# main.net
KiCad netlist of a schematic drawn in EAGLE
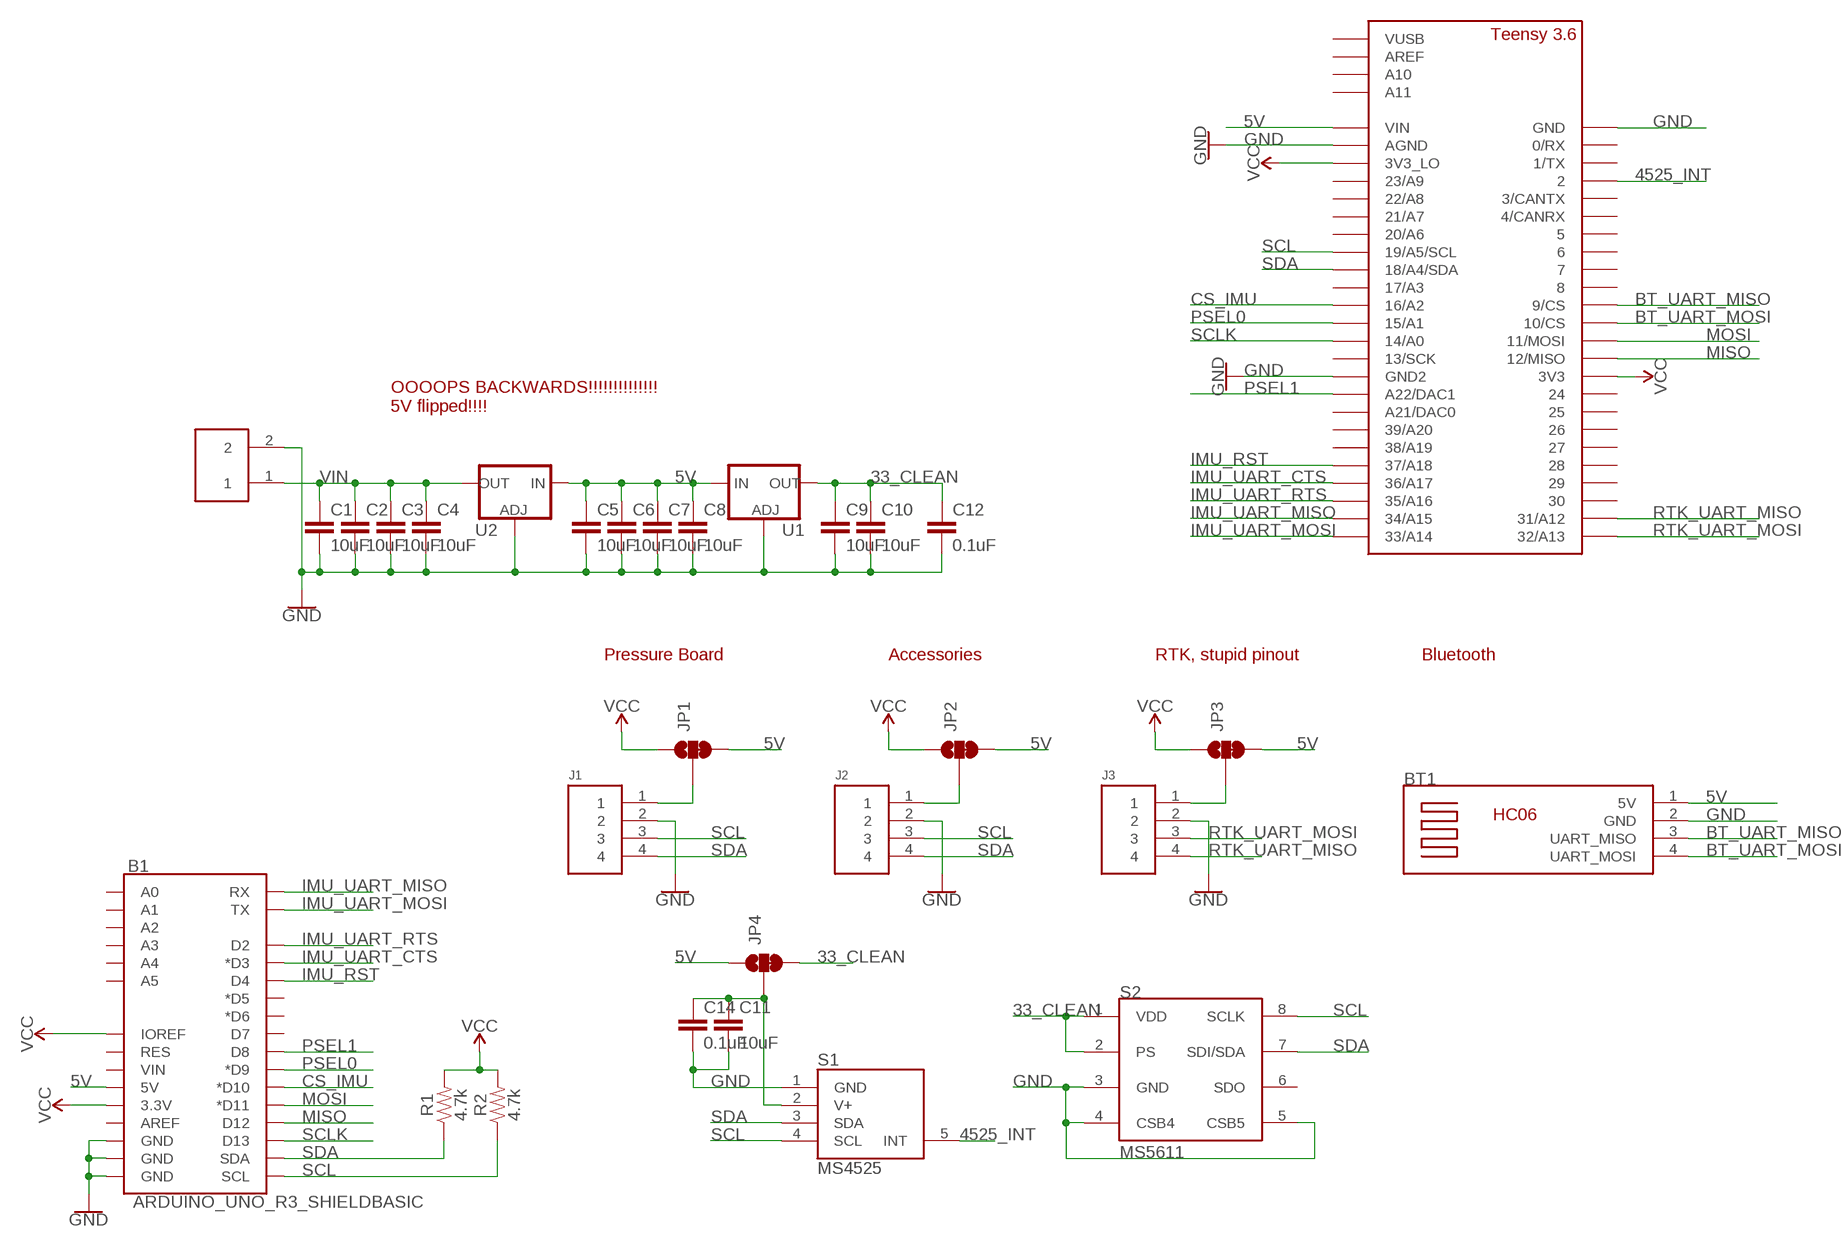
[diagram p0: schematic, sheet 1]

(export (version "E")
  (design (tool "Eeschema 10.0.6"))
  (components
    (comp (ref "B1")
      (value "ARDUINO_UNO_R3_SHIELDBASIC")
      (footprint "eagle-import:UNO_R3_SHIELD")
      (libsource (lib "eagle-import") (part "ARDUINO_UNO_R3_SHIELDBASIC"))
    )
    (comp (ref "BT1")
      (value "HC06")
      (footprint "eagle-import:HC06")
      (libsource (lib "eagle-import") (part "HC06"))
    )
    (comp (ref "C1")
      (value "10uF")
      (footprint "eagle-import:1206")
      (libsource (lib "eagle-import") (part "10UF-1206-6.3V-20%"))
    )
    (comp (ref "C2")
      (value "10uF")
      (footprint "eagle-import:1206")
      (libsource (lib "eagle-import") (part "10UF-1206-6.3V-20%"))
    )
    (comp (ref "C3")
      (value "10uF")
      (footprint "eagle-import:1206")
      (libsource (lib "eagle-import") (part "10UF-1206-6.3V-20%"))
    )
    (comp (ref "C4")
      (value "10uF")
      (footprint "eagle-import:1206")
      (libsource (lib "eagle-import") (part "10UF-1206-6.3V-20%"))
    )
    (comp (ref "C5")
      (value "10uF")
      (footprint "eagle-import:1206")
      (libsource (lib "eagle-import") (part "10UF-1206-6.3V-20%"))
    )
    (comp (ref "C6")
      (value "10uF")
      (footprint "eagle-import:1206")
      (libsource (lib "eagle-import") (part "10UF-1206-6.3V-20%"))
    )
    (comp (ref "C7")
      (value "10uF")
      (footprint "eagle-import:1206")
      (libsource (lib "eagle-import") (part "10UF-1206-6.3V-20%"))
    )
    (comp (ref "C8")
      (value "10uF")
      (footprint "eagle-import:1206")
      (libsource (lib "eagle-import") (part "10UF-1206-6.3V-20%"))
    )
    (comp (ref "C9")
      (value "10uF")
      (footprint "eagle-import:1206")
      (libsource (lib "eagle-import") (part "10UF-1206-6.3V-20%"))
    )
    (comp (ref "C10")
      (value "10uF")
      (footprint "eagle-import:1206")
      (libsource (lib "eagle-import") (part "10UF-1206-6.3V-20%"))
    )
    (comp (ref "C11")
      (value "10uF")
      (footprint "eagle-import:1206")
      (libsource (lib "eagle-import") (part "10UF-1206-6.3V-20%"))
    )
    (comp (ref "C12")
      (value "0.1uF")
      (footprint "eagle-import:0603")
      (libsource (lib "eagle-import") (part "0.1UF-0603-25V-5%"))
    )
    (comp (ref "C14")
      (value "0.1uF")
      (footprint "eagle-import:0603")
      (libsource (lib "eagle-import") (part "0.1UF-0603-25V-5%"))
    )
    (comp (ref "J1")
      (value "HEADER4VALULOK")
      (footprint "eagle-import:4PINVALULOK")
      (libsource (lib "eagle-import") (part "HEADER4VALULOK"))
    )
    (comp (ref "J2")
      (value "HEADER4VALULOK")
      (footprint "eagle-import:4PINVALULOK")
      (libsource (lib "eagle-import") (part "HEADER4VALULOK"))
    )
    (comp (ref "J3")
      (value "HEADER4VALULOK")
      (footprint "eagle-import:4PINVALULOK")
      (libsource (lib "eagle-import") (part "HEADER4VALULOK"))
    )
    (comp (ref "JP1")
      (value "JUMPER-SMT_3_1-NC_TRACE_SILK")
      (footprint "eagle-import:SMT-JUMPER_3_1-NC_TRACE_SILK")
      (libsource (lib "eagle-import") (part "JUMPER-SMT_3_1-NC_TRACE_SILK"))
    )
    (comp (ref "JP2")
      (value "JUMPER-SMT_3_1-NC_TRACE_SILK")
      (footprint "eagle-import:SMT-JUMPER_3_1-NC_TRACE_SILK")
      (libsource (lib "eagle-import") (part "JUMPER-SMT_3_1-NC_TRACE_SILK"))
    )
    (comp (ref "JP3")
      (value "JUMPER-SMT_3_1-NC_TRACE_SILK")
      (footprint "eagle-import:SMT-JUMPER_3_1-NC_TRACE_SILK")
      (libsource (lib "eagle-import") (part "JUMPER-SMT_3_1-NC_TRACE_SILK"))
    )
    (comp (ref "JP4")
      (value "JUMPER-SMT_3_1-NC_TRACE_SILK")
      (footprint "eagle-import:SMT-JUMPER_3_1-NC_TRACE_SILK")
      (libsource (lib "eagle-import") (part "JUMPER-SMT_3_1-NC_TRACE_SILK"))
    )
    (comp (ref "R1")
      (value "4.7k")
      (footprint "eagle-import:0603")
      (libsource (lib "eagle-import") (part "4.7KOHM-0603-1/10W-1%"))
    )
    (comp (ref "R2")
      (value "4.7k")
      (footprint "eagle-import:0603")
      (libsource (lib "eagle-import") (part "4.7KOHM-0603-1/10W-1%"))
    )
    (comp (ref "S1")
      (value "MS4525")
      (footprint "eagle-import:DIP1270W53P254L990H762Q8B")
      (libsource (lib "eagle-import") (part "MS4525MS4525DO"))
    )
    (comp (ref "S2")
      (value "MS5611")
      (footprint "eagle-import:MS5611")
      (libsource (lib "eagle-import") (part "MS5611"))
    )
    (comp (ref "U$1")
      (value "TEENSY_3.5/3.6_BASIC")
      (footprint "eagle-import:TEENSY_3.5_3.6_BASIC")
      (libsource (lib "eagle-import") (part "TEENSY_3.5/3.6_BASIC"))
    )
    (comp (ref "U$3")
      (value "HEADER2")
      (footprint "eagle-import:2PINVALULOK")
      (libsource (lib "eagle-import") (part "HEADER2"))
    )
    (comp (ref "U1")
      (value "V_REG_317SMD")
      (footprint "eagle-import:SOT223")
      (libsource (lib "eagle-import") (part "V_REG_317SMD"))
    )
    (comp (ref "U2")
      (value "V_REG_317DPACK")
      (footprint "eagle-import:V-REG_DPACK")
      (libsource (lib "eagle-import") (part "V_REG_317DPACK"))
    )
  )
  (nets
    (net (code "1") (name "/5V") (class "Default")
      (node (ref "B1") (pin "5V") (pinfunction "5V_5V") (pintype "bidirectional"))
      (node (ref "BT1") (pin "1") (pinfunction "5V_1") (pintype "bidirectional"))
      (node (ref "C5") (pin "1") (pinfunction "1_1") (pintype "passive"))
      (node (ref "C6") (pin "1") (pinfunction "1_1") (pintype "passive"))
      (node (ref "C7") (pin "1") (pinfunction "1_1") (pintype "passive"))
      (node (ref "C8") (pin "1") (pinfunction "1_1") (pintype "passive"))
      (node (ref "JP1") (pin "3") (pinfunction "3_3") (pintype "passive"))
      (node (ref "JP2") (pin "3") (pinfunction "3_3") (pintype "passive"))
      (node (ref "JP3") (pin "3") (pinfunction "3_3") (pintype "passive"))
      (node (ref "JP4") (pin "1") (pinfunction "1_1") (pintype "passive"))
      (node (ref "U$1") (pin "VIN") (pinfunction "VIN_VIN") (pintype "bidirectional"))
      (node (ref "U1") (pin "3") (pinfunction "IN_3") (pintype "input"))
      (node (ref "U2") (pin "3") (pinfunction "IN_3") (pintype "input"))
    )
    (net (code "2") (name "/33_CLEAN") (class "Default")
      (node (ref "C10") (pin "1") (pinfunction "1_1") (pintype "passive"))
      (node (ref "C12") (pin "1") (pinfunction "1_1") (pintype "passive"))
      (node (ref "C9") (pin "1") (pinfunction "1_1") (pintype "passive"))
      (node (ref "JP4") (pin "3") (pinfunction "3_3") (pintype "passive"))
      (node (ref "S2") (pin "1") (pinfunction "VDD_1") (pintype "bidirectional"))
      (node (ref "S2") (pin "2") (pinfunction "PS_2") (pintype "bidirectional"))
      (node (ref "U1") (pin "2") (pinfunction "OUT_2") (pintype "output"))
    )
    (net (code "3") (name "/4525_INT") (class "Default")
      (node (ref "S1") (pin "5") (pinfunction "INT_5") (pintype "bidirectional"))
      (node (ref "U$1") (pin "2") (pinfunction "2_2") (pintype "bidirectional"))
    )
    (net (code "4") (name "/BT_UART_MISO") (class "Default")
      (node (ref "BT1") (pin "3") (pinfunction "UART_MISO_3") (pintype "bidirectional"))
      (node (ref "U$1") (pin "9/CS") (pinfunction "9/CS_9/CS") (pintype "bidirectional"))
    )
    (net (code "5") (name "/BT_UART_MOSI") (class "Default")
      (node (ref "BT1") (pin "4") (pinfunction "UART_MOSI_4") (pintype "bidirectional"))
      (node (ref "U$1") (pin "10/CS") (pinfunction "10/CS_10/CS") (pintype "bidirectional"))
    )
    (net (code "6") (name "/CS_IMU") (class "Default")
      (node (ref "B1") (pin "D10") (pinfunction "*D10_D10") (pintype "bidirectional"))
      (node (ref "U$1") (pin "16/A2") (pinfunction "16/A2_16/A2") (pintype "bidirectional"))
    )
    (net (code "7") (name "/IMU_RST") (class "Default")
      (node (ref "B1") (pin "D4") (pinfunction "D4_D4") (pintype "bidirectional"))
      (node (ref "U$1") (pin "37/A18") (pinfunction "37/A18_37/A18") (pintype "bidirectional"))
    )
    (net (code "8") (name "/IMU_UART_CTS") (class "Default")
      (node (ref "B1") (pin "D3") (pinfunction "*D3_D3") (pintype "bidirectional"))
      (node (ref "U$1") (pin "36/A17") (pinfunction "36/A17_36/A17") (pintype "bidirectional"))
    )
    (net (code "9") (name "/IMU_UART_MISO") (class "Default")
      (node (ref "B1") (pin "RX") (pinfunction "RX_RX") (pintype "bidirectional"))
      (node (ref "U$1") (pin "34/A15") (pinfunction "34/A15_34/A15") (pintype "bidirectional"))
    )
    (net (code "10") (name "/IMU_UART_MOSI") (class "Default")
      (node (ref "B1") (pin "TX") (pinfunction "TX_TX") (pintype "bidirectional"))
      (node (ref "U$1") (pin "33/A14") (pinfunction "33/A14_33/A14") (pintype "bidirectional"))
    )
    (net (code "11") (name "/IMU_UART_RTS") (class "Default")
      (node (ref "B1") (pin "D2") (pinfunction "D2_D2") (pintype "bidirectional"))
      (node (ref "U$1") (pin "35/A16") (pinfunction "35/A16_35/A16") (pintype "bidirectional"))
    )
    (net (code "12") (name "/MISO") (class "Default")
      (node (ref "B1") (pin "D12") (pinfunction "D12_D12") (pintype "bidirectional"))
      (node (ref "U$1") (pin "12/MISO") (pinfunction "12/MISO_12/MISO") (pintype "bidirectional"))
    )
    (net (code "13") (name "/MOSI") (class "Default")
      (node (ref "B1") (pin "D11") (pinfunction "*D11_D11") (pintype "bidirectional"))
      (node (ref "U$1") (pin "11/MOSI") (pinfunction "11/MOSI_11/MOSI") (pintype "bidirectional"))
    )
    (net (code "14") (name "/PSEL0") (class "Default")
      (node (ref "B1") (pin "D9") (pinfunction "*D9_D9") (pintype "bidirectional"))
      (node (ref "U$1") (pin "15/A1") (pinfunction "15/A1_15/A1") (pintype "bidirectional"))
    )
    (net (code "15") (name "/PSEL1") (class "Default")
      (node (ref "B1") (pin "D8") (pinfunction "D8_D8") (pintype "bidirectional"))
      (node (ref "U$1") (pin "A22/DAC1") (pinfunction "A22/DAC1_A22/DAC1") (pintype "bidirectional"))
    )
    (net (code "16") (name "/RTK_UART_MISO") (class "Default")
      (node (ref "J3") (pin "4") (pinfunction "4_4") (pintype "bidirectional"))
      (node (ref "U$1") (pin "31/A12") (pinfunction "31/A12_31/A12") (pintype "bidirectional"))
    )
    (net (code "17") (name "/RTK_UART_MOSI") (class "Default")
      (node (ref "J3") (pin "3") (pinfunction "3_3") (pintype "bidirectional"))
      (node (ref "U$1") (pin "32/A13") (pinfunction "32/A13_32/A13") (pintype "bidirectional"))
    )
    (net (code "18") (name "/SCL") (class "Default")
      (node (ref "B1") (pin "SCL") (pinfunction "SCL_SCL") (pintype "bidirectional"))
      (node (ref "J1") (pin "3") (pinfunction "3_3") (pintype "bidirectional"))
      (node (ref "J2") (pin "3") (pinfunction "3_3") (pintype "bidirectional"))
      (node (ref "R2") (pin "1") (pinfunction "1_1") (pintype "passive"))
      (node (ref "S1") (pin "4") (pinfunction "SCL_4") (pintype "bidirectional"))
      (node (ref "S2") (pin "8") (pinfunction "SCLK_8") (pintype "bidirectional"))
      (node (ref "U$1") (pin "19/A5/SCL") (pinfunction "19/A5/SCL_19/A5/SCL") (pintype "bidirectional"))
    )
    (net (code "19") (name "/SCLK") (class "Default")
      (node (ref "B1") (pin "D13") (pinfunction "D13_D13") (pintype "bidirectional"))
      (node (ref "U$1") (pin "14/A0") (pinfunction "14/A0_14/A0") (pintype "bidirectional"))
    )
    (net (code "20") (name "/SDA") (class "Default")
      (node (ref "B1") (pin "SDA") (pinfunction "SDA_SDA") (pintype "bidirectional"))
      (node (ref "J1") (pin "4") (pinfunction "4_4") (pintype "bidirectional"))
      (node (ref "J2") (pin "4") (pinfunction "4_4") (pintype "bidirectional"))
      (node (ref "R1") (pin "1") (pinfunction "1_1") (pintype "passive"))
      (node (ref "S1") (pin "3") (pinfunction "SDA_3") (pintype "bidirectional"))
      (node (ref "S2") (pin "7") (pinfunction "SDI/SDA_7") (pintype "bidirectional"))
      (node (ref "U$1") (pin "18/A4/SDA") (pinfunction "18/A4/SDA_18/A4/SDA") (pintype "bidirectional"))
    )
    (net (code "21") (name "/VIN") (class "Default")
      (node (ref "C1") (pin "1") (pinfunction "1_1") (pintype "passive"))
      (node (ref "C2") (pin "1") (pinfunction "1_1") (pintype "passive"))
      (node (ref "C3") (pin "1") (pinfunction "1_1") (pintype "passive"))
      (node (ref "C4") (pin "1") (pinfunction "1_1") (pintype "passive"))
      (node (ref "U$3") (pin "1") (pinfunction "1_1") (pintype "bidirectional"))
      (node (ref "U2") (pin "4") (pinfunction "OUT_4") (pintype "output"))
    )
    (net (code "22") (name "GND") (class "Default")
      (node (ref "B1") (pin "GND@0") (pinfunction "GND_GND@0") (pintype "bidirectional"))
      (node (ref "B1") (pin "GND@1") (pinfunction "GND_GND@1") (pintype "bidirectional"))
      (node (ref "B1") (pin "GND@2") (pinfunction "GND_GND@2") (pintype "bidirectional"))
      (node (ref "BT1") (pin "2") (pinfunction "GND_2") (pintype "bidirectional"))
      (node (ref "C1") (pin "2") (pinfunction "2_2") (pintype "passive"))
      (node (ref "C10") (pin "2") (pinfunction "2_2") (pintype "passive"))
      (node (ref "C11") (pin "2") (pinfunction "2_2") (pintype "passive"))
      (node (ref "C12") (pin "2") (pinfunction "2_2") (pintype "passive"))
      (node (ref "C14") (pin "2") (pinfunction "2_2") (pintype "passive"))
      (node (ref "C2") (pin "2") (pinfunction "2_2") (pintype "passive"))
      (node (ref "C3") (pin "2") (pinfunction "2_2") (pintype "passive"))
      (node (ref "C4") (pin "2") (pinfunction "2_2") (pintype "passive"))
      (node (ref "C5") (pin "2") (pinfunction "2_2") (pintype "passive"))
      (node (ref "C6") (pin "2") (pinfunction "2_2") (pintype "passive"))
      (node (ref "C7") (pin "2") (pinfunction "2_2") (pintype "passive"))
      (node (ref "C8") (pin "2") (pinfunction "2_2") (pintype "passive"))
      (node (ref "C9") (pin "2") (pinfunction "2_2") (pintype "passive"))
      (node (ref "J1") (pin "2") (pinfunction "2_2") (pintype "bidirectional"))
      (node (ref "J2") (pin "2") (pinfunction "2_2") (pintype "bidirectional"))
      (node (ref "J3") (pin "2") (pinfunction "2_2") (pintype "bidirectional"))
      (node (ref "S1") (pin "1") (pinfunction "GND_1") (pintype "bidirectional"))
      (node (ref "S2") (pin "3") (pinfunction "GND_3") (pintype "bidirectional"))
      (node (ref "S2") (pin "4") (pinfunction "CSB4_4") (pintype "bidirectional"))
      (node (ref "S2") (pin "5") (pinfunction "CSB5_5") (pintype "bidirectional"))
      (node (ref "U$1") (pin "AGND") (pinfunction "AGND_AGND") (pintype "bidirectional"))
      (node (ref "U$1") (pin "GND") (pinfunction "GND_GND") (pintype "bidirectional"))
      (node (ref "U$1") (pin "GND2") (pinfunction "GND2_GND2") (pintype "bidirectional"))
      (node (ref "U$3") (pin "2") (pinfunction "2_2") (pintype "bidirectional"))
      (node (ref "U1") (pin "1") (pinfunction "ADJ_1") (pintype "input"))
      (node (ref "U2") (pin "1") (pinfunction "ADJ_1") (pintype "input"))
    )
    (net (code "23") (name "Net-(J1-Pad1)") (class "Default")
      (node (ref "J1") (pin "1") (pinfunction "1_1") (pintype "bidirectional"))
      (node (ref "JP1") (pin "2") (pinfunction "2_2") (pintype "passive"))
    )
    (net (code "24") (name "Net-(J2-Pad1)") (class "Default")
      (node (ref "J2") (pin "1") (pinfunction "1_1") (pintype "bidirectional"))
      (node (ref "JP2") (pin "2") (pinfunction "2_2") (pintype "passive"))
    )
    (net (code "25") (name "Net-(J3-Pad1)") (class "Default")
      (node (ref "J3") (pin "1") (pinfunction "1_1") (pintype "bidirectional"))
      (node (ref "JP3") (pin "2") (pinfunction "2_2") (pintype "passive"))
    )
    (net (code "26") (name "Net-(S1-V+)") (class "Default")
      (node (ref "C11") (pin "1") (pinfunction "1_1") (pintype "passive"))
      (node (ref "C14") (pin "1") (pinfunction "1_1") (pintype "passive"))
      (node (ref "JP4") (pin "2") (pinfunction "2_2") (pintype "passive"))
      (node (ref "S1") (pin "2") (pinfunction "V+_2") (pintype "bidirectional"))
    )
    (net (code "27") (name "VCC") (class "Default")
      (node (ref "B1") (pin "3.3V") (pinfunction "3.3V_3.3V") (pintype "bidirectional"))
      (node (ref "B1") (pin "IOREF") (pinfunction "IOREF_IOREF") (pintype "bidirectional"))
      (node (ref "JP1") (pin "1") (pinfunction "1_1") (pintype "passive"))
      (node (ref "JP2") (pin "1") (pinfunction "1_1") (pintype "passive"))
      (node (ref "JP3") (pin "1") (pinfunction "1_1") (pintype "passive"))
      (node (ref "R1") (pin "2") (pinfunction "2_2") (pintype "passive"))
      (node (ref "R2") (pin "2") (pinfunction "2_2") (pintype "passive"))
      (node (ref "U$1") (pin "3V3") (pinfunction "3V3_3V3") (pintype "bidirectional"))
      (node (ref "U$1") (pin "3V3_LO") (pinfunction "3V3_LO_3V3_LO") (pintype "bidirectional"))
    )
    (net (code "28") (name "unconnected-(B1-*D5-PadD5)") (class "Default")
      (node (ref "B1") (pin "D5") (pinfunction "*D5_D5") (pintype "bidirectional"))
    )
    (net (code "29") (name "unconnected-(B1-*D6-PadD6)") (class "Default")
      (node (ref "B1") (pin "D6") (pinfunction "*D6_D6") (pintype "bidirectional"))
    )
    (net (code "30") (name "unconnected-(B1-PadA0)") (class "Default")
      (node (ref "B1") (pin "A0") (pinfunction "A0_A0") (pintype "bidirectional"))
    )
    (net (code "31") (name "unconnected-(B1-PadA1)") (class "Default")
      (node (ref "B1") (pin "A1") (pinfunction "A1_A1") (pintype "bidirectional"))
    )
    (net (code "32") (name "unconnected-(B1-PadA2)") (class "Default")
      (node (ref "B1") (pin "A2") (pinfunction "A2_A2") (pintype "bidirectional"))
    )
    (net (code "33") (name "unconnected-(B1-PadA3)") (class "Default")
      (node (ref "B1") (pin "A3") (pinfunction "A3_A3") (pintype "bidirectional"))
    )
    (net (code "34") (name "unconnected-(B1-PadA4)") (class "Default")
      (node (ref "B1") (pin "A4") (pinfunction "A4_A4") (pintype "bidirectional"))
    )
    (net (code "35") (name "unconnected-(B1-PadA5)") (class "Default")
      (node (ref "B1") (pin "A5") (pinfunction "A5_A5") (pintype "bidirectional"))
    )
    (net (code "36") (name "unconnected-(B1-PadAREF)") (class "Default")
      (node (ref "B1") (pin "AREF") (pinfunction "AREF_AREF") (pintype "bidirectional"))
    )
    (net (code "37") (name "unconnected-(B1-PadD7)") (class "Default")
      (node (ref "B1") (pin "D7") (pinfunction "D7_D7") (pintype "bidirectional"))
    )
    (net (code "38") (name "unconnected-(B1-PadRES)") (class "Default")
      (node (ref "B1") (pin "RES") (pinfunction "RES_RES") (pintype "bidirectional"))
    )
    (net (code "39") (name "unconnected-(B1-PadVIN)") (class "Default")
      (node (ref "B1") (pin "VIN") (pinfunction "VIN_VIN") (pintype "bidirectional"))
    )
    (net (code "40") (name "unconnected-(S2-SDO-Pad6)") (class "Default")
      (node (ref "S2") (pin "6") (pinfunction "SDO_6") (pintype "bidirectional"))
    )
    (net (code "41") (name "unconnected-(U$1-A21{slash}DAC0-Pad21{slash}DAC0)") (class "Default")
      (node (ref "U$1") (pin "21/DAC0") (pinfunction "A21/DAC0_21/DAC0") (pintype "bidirectional"))
    )
    (net (code "42") (name "unconnected-(U$1-Pad0{slash}RX)") (class "Default")
      (node (ref "U$1") (pin "0/RX") (pinfunction "0/RX_0/RX") (pintype "bidirectional"))
    )
    (net (code "43") (name "unconnected-(U$1-Pad1{slash}TX)") (class "Default")
      (node (ref "U$1") (pin "1/TX") (pinfunction "1/TX_1/TX") (pintype "bidirectional"))
    )
    (net (code "44") (name "unconnected-(U$1-Pad3{slash}CANTX)") (class "Default")
      (node (ref "U$1") (pin "3/CANTX") (pinfunction "3/CANTX_3/CANTX") (pintype "bidirectional"))
    )
    (net (code "45") (name "unconnected-(U$1-Pad4{slash}CANRX)") (class "Default")
      (node (ref "U$1") (pin "4/CANRX") (pinfunction "4/CANRX_4/CANRX") (pintype "bidirectional"))
    )
    (net (code "46") (name "unconnected-(U$1-Pad5)") (class "Default")
      (node (ref "U$1") (pin "5") (pinfunction "5_5") (pintype "bidirectional"))
    )
    (net (code "47") (name "unconnected-(U$1-Pad6)") (class "Default")
      (node (ref "U$1") (pin "6") (pinfunction "6_6") (pintype "bidirectional"))
    )
    (net (code "48") (name "unconnected-(U$1-Pad7)") (class "Default")
      (node (ref "U$1") (pin "7") (pinfunction "7_7") (pintype "bidirectional"))
    )
    (net (code "49") (name "unconnected-(U$1-Pad8)") (class "Default")
      (node (ref "U$1") (pin "8") (pinfunction "8_8") (pintype "bidirectional"))
    )
    (net (code "50") (name "unconnected-(U$1-Pad13{slash}SCK)") (class "Default")
      (node (ref "U$1") (pin "13/SCK") (pinfunction "13/SCK_13/SCK") (pintype "bidirectional"))
    )
    (net (code "51") (name "unconnected-(U$1-Pad17{slash}A3)") (class "Default")
      (node (ref "U$1") (pin "17/A3") (pinfunction "17/A3_17/A3") (pintype "bidirectional"))
    )
    (net (code "52") (name "unconnected-(U$1-Pad20{slash}A6)") (class "Default")
      (node (ref "U$1") (pin "20/A6") (pinfunction "20/A6_20/A6") (pintype "bidirectional"))
    )
    (net (code "53") (name "unconnected-(U$1-Pad21{slash}A7)") (class "Default")
      (node (ref "U$1") (pin "21/A7") (pinfunction "21/A7_21/A7") (pintype "bidirectional"))
    )
    (net (code "54") (name "unconnected-(U$1-Pad22{slash}A8)") (class "Default")
      (node (ref "U$1") (pin "22/A8") (pinfunction "22/A8_22/A8") (pintype "bidirectional"))
    )
    (net (code "55") (name "unconnected-(U$1-Pad23{slash}A9)") (class "Default")
      (node (ref "U$1") (pin "23/A9") (pinfunction "23/A9_23/A9") (pintype "bidirectional"))
    )
    (net (code "56") (name "unconnected-(U$1-Pad24)") (class "Default")
      (node (ref "U$1") (pin "24") (pinfunction "24_24") (pintype "bidirectional"))
    )
    (net (code "57") (name "unconnected-(U$1-Pad25)") (class "Default")
      (node (ref "U$1") (pin "25") (pinfunction "25_25") (pintype "bidirectional"))
    )
    (net (code "58") (name "unconnected-(U$1-Pad26)") (class "Default")
      (node (ref "U$1") (pin "26") (pinfunction "26_26") (pintype "bidirectional"))
    )
    (net (code "59") (name "unconnected-(U$1-Pad27)") (class "Default")
      (node (ref "U$1") (pin "27") (pinfunction "27_27") (pintype "bidirectional"))
    )
    (net (code "60") (name "unconnected-(U$1-Pad28)") (class "Default")
      (node (ref "U$1") (pin "28") (pinfunction "28_28") (pintype "bidirectional"))
    )
    (net (code "61") (name "unconnected-(U$1-Pad29)") (class "Default")
      (node (ref "U$1") (pin "29") (pinfunction "29_29") (pintype "bidirectional"))
    )
    (net (code "62") (name "unconnected-(U$1-Pad30)") (class "Default")
      (node (ref "U$1") (pin "30") (pinfunction "30_30") (pintype "bidirectional"))
    )
    (net (code "63") (name "unconnected-(U$1-Pad38{slash}A19)") (class "Default")
      (node (ref "U$1") (pin "38/A19") (pinfunction "38/A19_38/A19") (pintype "bidirectional"))
    )
    (net (code "64") (name "unconnected-(U$1-Pad39{slash}A20)") (class "Default")
      (node (ref "U$1") (pin "39/A20") (pinfunction "39/A20_39/A20") (pintype "bidirectional"))
    )
    (net (code "65") (name "unconnected-(U$1-PadA10)") (class "Default")
      (node (ref "U$1") (pin "A10") (pinfunction "A10_A10") (pintype "bidirectional"))
    )
    (net (code "66") (name "unconnected-(U$1-PadA11)") (class "Default")
      (node (ref "U$1") (pin "A11") (pinfunction "A11_A11") (pintype "bidirectional"))
    )
    (net (code "67") (name "unconnected-(U$1-PadAREF)") (class "Default")
      (node (ref "U$1") (pin "AREF") (pinfunction "AREF_AREF") (pintype "bidirectional"))
    )
    (net (code "68") (name "unconnected-(U$1-PadVUSB)") (class "Default")
      (node (ref "U$1") (pin "VUSB") (pinfunction "VUSB_VUSB") (pintype "bidirectional"))
    )
  )
)
